# input_hv.net
KiCad netlist of a schematic drawn in Altium Designer
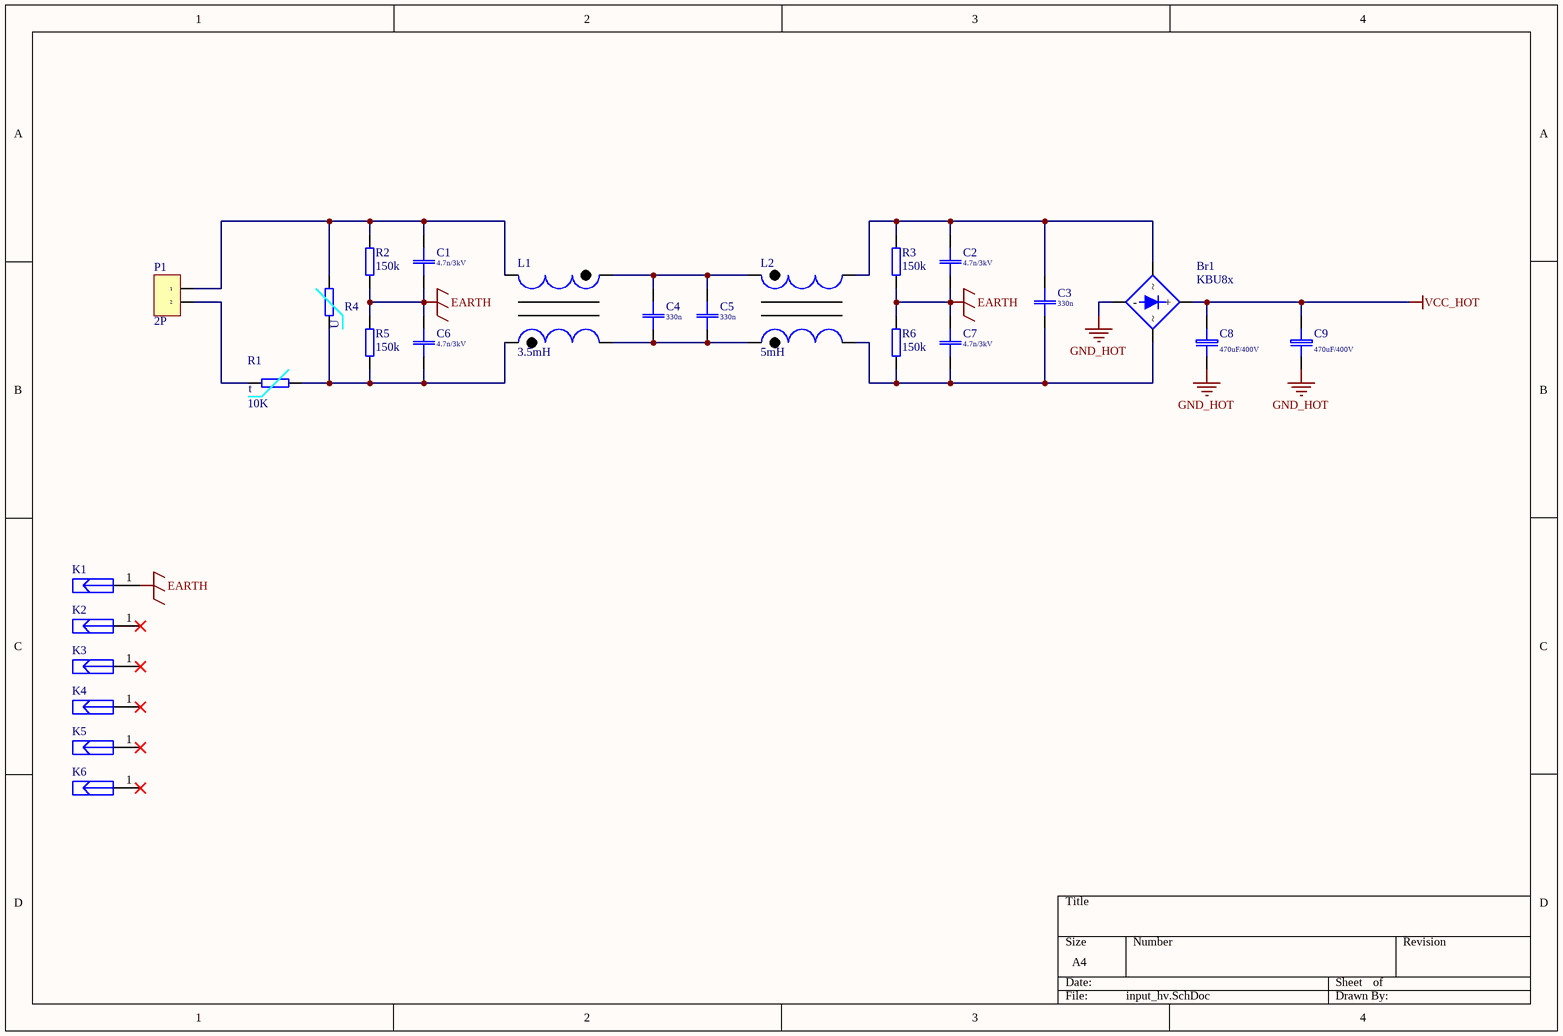
[diagram p0: input_hv.SchDoc]

(export (version "E")
  (design (tool "Eeschema 10.0.6"))
  (components
    (comp (ref "Br1")
      (value "KBU8x")
      (footprint "KBU-200 h22mm")
      (description "Грец  8A")
      (libsource (lib "Diodes-Bridge") (part "KBU"))
    )
    (comp (ref "C1")
      (value "4.7n/3kV")
      (footprint "Cer-Disk-D8-R7.62")
      (description "2.2n 2kV Y5P")
      (libsource (lib "Cap") (part "Cer Disc HV 2.2n 2kV"))
    )
    (comp (ref "C2")
      (value "4.7n/3kV")
      (footprint "Cer-Disk-D8-R7.62")
      (description "2.2n 2kV Y5P")
      (libsource (lib "Cap") (part "Cer Disc HV 2.2n 2kV"))
    )
    (comp (ref "C3")
      (value "330n")
      (footprint "MKP X2 100nF 275V AC")
      (description "X2 250V AC")
      (libsource (lib "Cap") (part "X2 100n 275V AC"))
    )
    (comp (ref "C4")
      (value "330n")
      (footprint "MKP X2 100nF 275V AC")
      (description "X2 250V AC")
      (libsource (lib "Cap") (part "X2 100n 275V AC"))
    )
    (comp (ref "C5")
      (value "330n")
      (footprint "MKP X2 100nF 275V AC")
      (description "X2 250V AC")
      (libsource (lib "Cap") (part "X2 100n 275V AC"))
    )
    (comp (ref "C6")
      (value "4.7n/3kV")
      (footprint "Cer-Disk-D8-R7.62")
      (description "2.2n 2kV Y5P")
      (libsource (lib "Cap") (part "Cer Disc HV 2.2n 2kV"))
    )
    (comp (ref "C7")
      (value "4.7n/3kV")
      (footprint "Cer-Disk-D8-R7.62")
      (description "2.2n 2kV Y5P")
      (libsource (lib "Cap") (part "Cer Disc HV 2.2n 2kV"))
    )
    (comp (ref "C8")
      (value "470uF/400V")
      (footprint "CAP: D25C10H50")
      (libsource (lib "PASSIVE") (part "C_EL"))
    )
    (comp (ref "C9")
      (value "470uF/400V")
      (footprint "CAP: D25C10H50")
      (libsource (lib "PASSIVE") (part "C_EL"))
    )
    (comp (ref "K1") (value "~") (footprint "CON: TH 3.5mm") (libsource (lib "OTHER") (part "PCB CON")))
    (comp (ref "K2") (value "~") (footprint "CON: TH 3.5mm") (libsource (lib "OTHER") (part "PCB CON")))
    (comp (ref "K3") (value "~") (footprint "CON: TH 3.5mm") (libsource (lib "OTHER") (part "PCB CON")))
    (comp (ref "K4") (value "~") (footprint "CON: TH 3.5mm") (libsource (lib "OTHER") (part "PCB CON")))
    (comp (ref "K5") (value "~") (footprint "CON: TH 3.5mm") (libsource (lib "OTHER") (part "PCB CON")))
    (comp (ref "K6") (value "~") (footprint "CON: TH 3.5mm") (libsource (lib "OTHER") (part "PCB CON")))
    (comp (ref "L1")
      (value "3.5mH")
      (footprint "IND: R26.9/14.7/11.2 (H)")
      (libsource (lib "EMI") (part "DROSSEL_1"))
    )
    (comp (ref "L2")
      (value "5mH")
      (footprint "IND: R26.9/14.7/11.2 (H)")
      (libsource (lib "EMI") (part "DROSSEL"))
    )
    (comp (ref "P1") (value "2P") (footprint "CON: 2P V 3.5mm") (libsource (lib "CONNECTOR") (part "2P")))
    (comp (ref "R1")
      (value "10K")
      (footprint "RES: NTC D15-R7.62")
      (libsource (lib "PASSIVE") (part "R_NTC"))
    )
    (comp (ref "R2") (value "150k") (footprint "RES: 0.125W H") (libsource (lib "PASSIVE") (part "R_DIP")))
    (comp (ref "R3") (value "150k") (footprint "RES: 0.125W H") (libsource (lib "PASSIVE") (part "R_DIP")))
    (comp (ref "R4") (value "VAR") (footprint "RES: VAR 11K 300") (libsource (lib "PASSIVE") (part "R_VAR")))
    (comp (ref "R5") (value "150k") (footprint "RES: 0.125W H") (libsource (lib "PASSIVE") (part "R_DIP")))
    (comp (ref "R6") (value "150k") (footprint "RES: 0.125W H") (libsource (lib "PASSIVE") (part "R_DIP")))
  )
  (nets
    (net (code "1") (name "EARTH") (class "Default")
      (node (ref "C1") (pin "2") (pinfunction "2_2") (pintype "passive"))
      (node (ref "C2") (pin "2") (pinfunction "2_2") (pintype "passive"))
      (node (ref "C6") (pin "1") (pinfunction "1_1") (pintype "passive"))
      (node (ref "C7") (pin "1") (pinfunction "1_1") (pintype "passive"))
      (node (ref "K1") (pin "1") (pintype "passive"))
      (node (ref "R2") (pin "2") (pinfunction "2_2") (pintype "passive"))
      (node (ref "R3") (pin "2") (pinfunction "2_2") (pintype "passive"))
      (node (ref "R5") (pin "1") (pinfunction "1_1") (pintype "passive"))
      (node (ref "R6") (pin "1") (pinfunction "1_1") (pintype "passive"))
    )
    (net (code "2") (name "GND_HOT") (class "Default")
      (node (ref "Br1") (pin "2") (pinfunction "-_2") (pintype "passive"))
      (node (ref "C8") (pin "2") (pinfunction "-_2") (pintype "passive"))
      (node (ref "C9") (pin "2") (pinfunction "-_2") (pintype "passive"))
    )
    (net (code "3") (name "Net-(Br1-~-Pad3)") (class "Default")
      (node (ref "Br1") (pin "3") (pinfunction "~_3") (pintype "passive"))
      (node (ref "C3") (pin "2") (pinfunction "2_2") (pintype "passive"))
      (node (ref "C7") (pin "2") (pinfunction "2_2") (pintype "passive"))
      (node (ref "L2") (pin "4") (pinfunction "4_4") (pintype "passive"))
      (node (ref "R6") (pin "2") (pinfunction "2_2") (pintype "passive"))
    )
    (net (code "4") (name "Net-(Br1-~-Pad4)") (class "Default")
      (node (ref "Br1") (pin "4") (pinfunction "~_4") (pintype "passive"))
      (node (ref "C2") (pin "1") (pinfunction "1_1") (pintype "passive"))
      (node (ref "C3") (pin "1") (pinfunction "1_1") (pintype "passive"))
      (node (ref "L2") (pin "2") (pinfunction "2_2") (pintype "passive"))
      (node (ref "R3") (pin "1") (pinfunction "1_1") (pintype "passive"))
    )
    (net (code "5") (name "Net-(C1-Pad1)") (class "Default")
      (node (ref "C1") (pin "1") (pinfunction "1_1") (pintype "passive"))
      (node (ref "L1") (pin "1") (pinfunction "1_1") (pintype "passive"))
      (node (ref "P1") (pin "1") (pinfunction "1_1") (pintype "passive"))
      (node (ref "R2") (pin "1") (pinfunction "1_1") (pintype "passive"))
      (node (ref "R4") (pin "2") (pinfunction "2_2") (pintype "passive"))
    )
    (net (code "6") (name "Net-(C4-Pad1)") (class "Default")
      (node (ref "C4") (pin "1") (pinfunction "1_1") (pintype "passive"))
      (node (ref "C5") (pin "1") (pinfunction "1_1") (pintype "passive"))
      (node (ref "L1") (pin "2") (pinfunction "2_2") (pintype "passive"))
      (node (ref "L2") (pin "1") (pinfunction "1_1") (pintype "passive"))
    )
    (net (code "7") (name "Net-(C4-Pad2)") (class "Default")
      (node (ref "C4") (pin "2") (pinfunction "2_2") (pintype "passive"))
      (node (ref "C5") (pin "2") (pinfunction "2_2") (pintype "passive"))
      (node (ref "L1") (pin "4") (pinfunction "4_4") (pintype "passive"))
      (node (ref "L2") (pin "3") (pinfunction "3_3") (pintype "passive"))
    )
    (net (code "8") (name "Net-(C6-Pad2)") (class "Default")
      (node (ref "C6") (pin "2") (pinfunction "2_2") (pintype "passive"))
      (node (ref "L1") (pin "3") (pinfunction "3_3") (pintype "passive"))
      (node (ref "R1") (pin "2") (pinfunction "2_2") (pintype "passive"))
      (node (ref "R4") (pin "1") (pinfunction "1_1") (pintype "passive"))
      (node (ref "R5") (pin "2") (pinfunction "2_2") (pintype "passive"))
    )
    (net (code "9") (name "Net-(P1-Pad2)") (class "Default")
      (node (ref "P1") (pin "2") (pinfunction "2_2") (pintype "passive"))
      (node (ref "R1") (pin "1") (pinfunction "1_1") (pintype "passive"))
    )
    (net (code "10") (name "VCC_HOT") (class "Default")
      (node (ref "Br1") (pin "1") (pinfunction "+_1") (pintype "passive"))
      (node (ref "C8") (pin "1") (pinfunction "+_1") (pintype "passive"))
      (node (ref "C9") (pin "1") (pinfunction "+_1") (pintype "passive"))
    )
    (net (code "11") (name "unconnected-(K2-Pad1)") (class "Default")
      (node (ref "K2") (pin "1") (pintype "passive+no_connect"))
    )
    (net (code "12") (name "unconnected-(K3-Pad1)") (class "Default")
      (node (ref "K3") (pin "1") (pintype "passive+no_connect"))
    )
    (net (code "13") (name "unconnected-(K4-Pad1)") (class "Default")
      (node (ref "K4") (pin "1") (pintype "passive+no_connect"))
    )
    (net (code "14") (name "unconnected-(K5-Pad1)") (class "Default")
      (node (ref "K5") (pin "1") (pintype "passive+no_connect"))
    )
    (net (code "15") (name "unconnected-(K6-Pad1)") (class "Default")
      (node (ref "K6") (pin "1") (pintype "passive+no_connect"))
    )
  )
)
